# 04-Front_Panel_SFP_2.net
KiCad netlist of a schematic drawn in Altium Designer
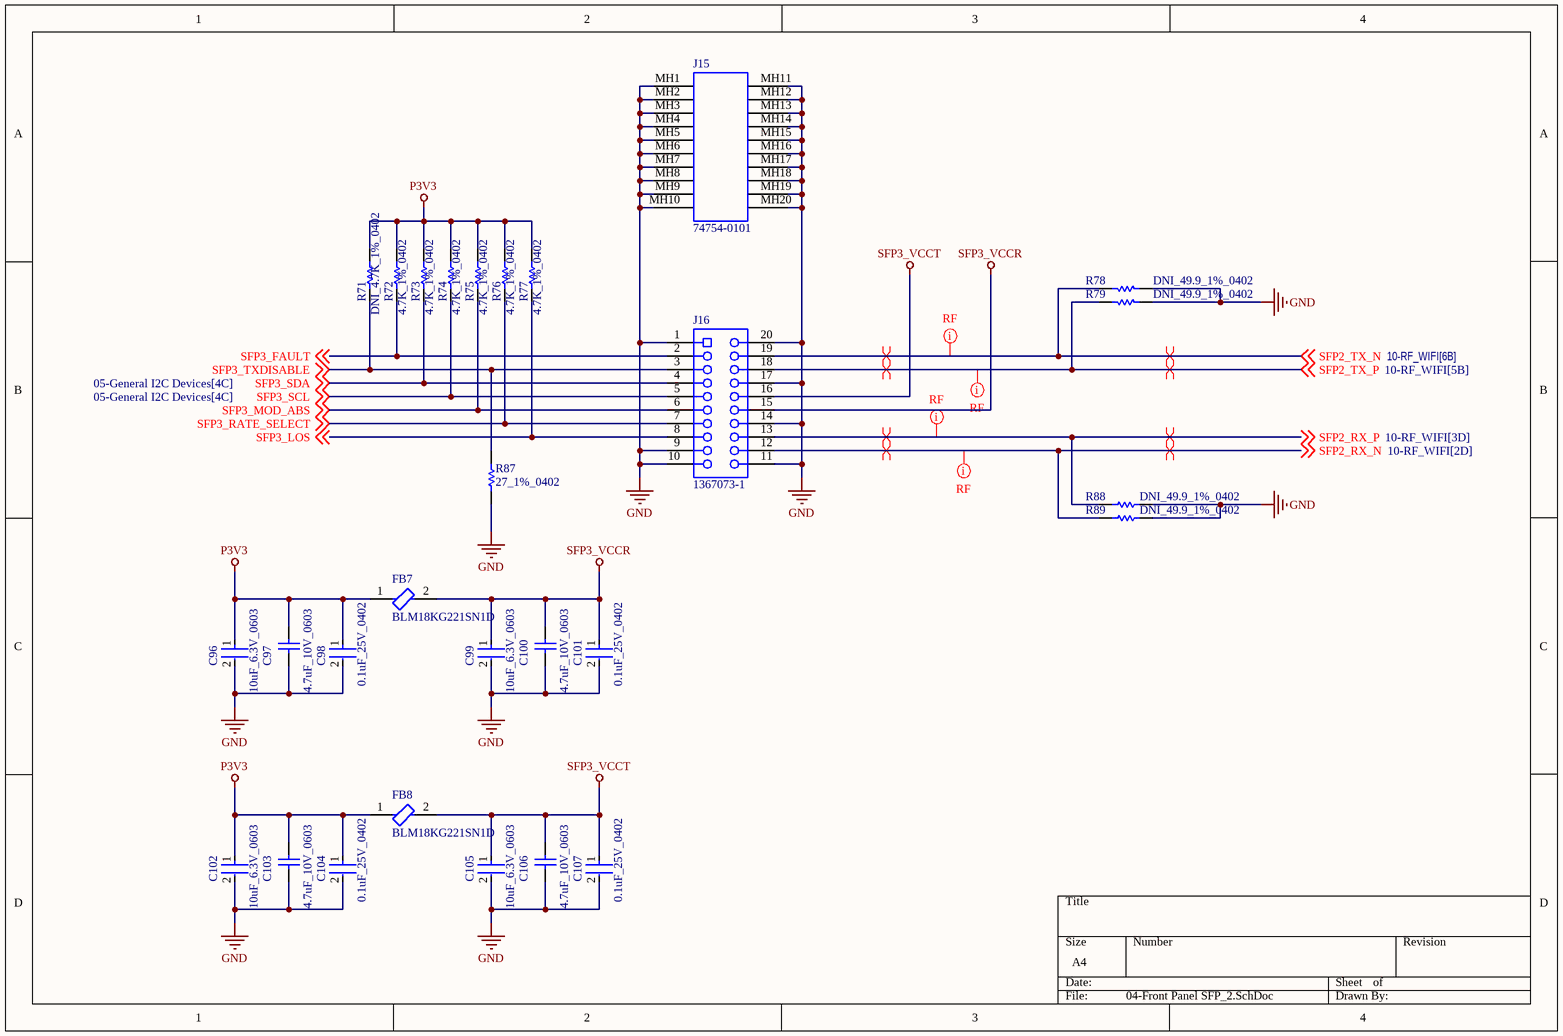
[diagram p0: 04-Front Panel SFP_2.SchDoc]

(export (version "E")
  (design (tool "Eeschema 10.0.6"))
  (components
    (comp (ref "C96")
      (value "10uF_6.3V_0603")
      (footprint "FP-C0603C106M9PACTU-MFG")
      (description "CAP CER 10UF 6.3V X5R 0603")
      (fields
        (field (name "MANUFACTURER PART NUMBER") "C0603C106M9PACTU")
        (field (name "MANUFACTURER") "Kemet")
      )
      (libsource (lib "Altium Content Vault") (part "b4654b650e69147ec39a6b967a45e02"))
    )
    (comp (ref "C97")
      (value "4.7uF_10V_0603")
      (footprint "CAPC1608X87X35NL15T15")
      (fields (field (name "PART NUMBER") "C0603C475K8PACTU") (field (name "MANUFACTURER") "Kemet"))
      (libsource (lib "Altium Content Vault") (part "CAP"))
    )
    (comp (ref "C98")
      (value "0.1uF_25V_0402")
      (footprint "FP-0402-L_1_0_1-W_0_5_0_1-IPC_C")
      (description "General Purpose Ceramic Capacitor, 0402, 100nF, 10%, X7R, 15%, 25V")
      (fields (field (name "VOLTAGE") "25V") (field (name "TOLERANCE") "10%"))
      (libsource (lib "Altium Content Vault") (part "b4654b650e69147ec39a6b967a45e02"))
    )
    (comp (ref "C99")
      (value "10uF_6.3V_0603")
      (footprint "FP-C0603C106M9PACTU-MFG")
      (description "CAP CER 10UF 6.3V X5R 0603")
      (fields
        (field (name "MANUFACTURER PART NUMBER") "C0603C106M9PACTU")
        (field (name "MANUFACTURER") "Kemet")
      )
      (libsource (lib "Altium Content Vault") (part "b4654b650e69147ec39a6b967a45e02"))
    )
    (comp (ref "C100")
      (value "4.7uF_10V_0603")
      (footprint "CAPC1608X87X35NL15T15")
      (fields (field (name "PART NUMBER") "C0603C475K8PACTU") (field (name "MANUFACTURER") "Kemet"))
      (libsource (lib "Altium Content Vault") (part "CAP"))
    )
    (comp (ref "C101")
      (value "0.1uF_25V_0402")
      (footprint "FP-0402-L_1_0_1-W_0_5_0_1-IPC_C")
      (description "General Purpose Ceramic Capacitor, 0402, 100nF, 10%, X7R, 15%, 25V")
      (fields (field (name "VOLTAGE") "25V") (field (name "TOLERANCE") "10%"))
      (libsource (lib "Altium Content Vault") (part "b4654b650e69147ec39a6b967a45e02"))
    )
    (comp (ref "C102")
      (value "10uF_6.3V_0603")
      (footprint "FP-C0603C106M9PACTU-MFG")
      (description "CAP CER 10UF 6.3V X5R 0603")
      (fields
        (field (name "MANUFACTURER PART NUMBER") "C0603C106M9PACTU")
        (field (name "MANUFACTURER") "Kemet")
      )
      (libsource (lib "Altium Content Vault") (part "b4654b650e69147ec39a6b967a45e02"))
    )
    (comp (ref "C103")
      (value "4.7uF_10V_0603")
      (footprint "CAPC1608X87X35NL15T15")
      (fields (field (name "PART NUMBER") "C0603C475K8PACTU") (field (name "MANUFACTURER") "Kemet"))
      (libsource (lib "Altium Content Vault") (part "CAP"))
    )
    (comp (ref "C104")
      (value "0.1uF_25V_0402")
      (footprint "FP-0402-L_1_0_1-W_0_5_0_1-IPC_C")
      (description "General Purpose Ceramic Capacitor, 0402, 100nF, 10%, X7R, 15%, 25V")
      (fields (field (name "VOLTAGE") "25V") (field (name "TOLERANCE") "10%"))
      (libsource (lib "Altium Content Vault") (part "b4654b650e69147ec39a6b967a45e02"))
    )
    (comp (ref "C105")
      (value "10uF_6.3V_0603")
      (footprint "FP-C0603C106M9PACTU-MFG")
      (description "CAP CER 10UF 6.3V X5R 0603")
      (fields
        (field (name "MANUFACTURER PART NUMBER") "C0603C106M9PACTU")
        (field (name "MANUFACTURER") "Kemet")
      )
      (libsource (lib "Altium Content Vault") (part "b4654b650e69147ec39a6b967a45e02"))
    )
    (comp (ref "C106")
      (value "4.7uF_10V_0603")
      (footprint "CAPC1608X87X35NL15T15")
      (fields (field (name "PART NUMBER") "C0603C475K8PACTU") (field (name "MANUFACTURER") "Kemet"))
      (libsource (lib "Altium Content Vault") (part "CAP"))
    )
    (comp (ref "C107")
      (value "0.1uF_25V_0402")
      (footprint "FP-0402-L_1_0_1-W_0_5_0_1-IPC_C")
      (description "General Purpose Ceramic Capacitor, 0402, 100nF, 10%, X7R, 15%, 25V")
      (fields (field (name "VOLTAGE") "25V") (field (name "TOLERANCE") "10%"))
      (libsource (lib "Altium Content Vault") (part "b4654b650e69147ec39a6b967a45e02"))
    )
    (comp (ref "FB7")
      (value "BLM18KG221SN1D")
      (footprint "FP-BLM18-0_15-t0_8-IPC_B")
      (description "Chip Ferrite Bead, 0603, 220Ω @ 100MHz, 0.05Ω, 25%, 2.2A")
      (fields (field (name "TOLERANCE") "25%"))
      (libsource (lib "Altium Content Vault") (part "5f30dd21d616792df468990f7003faa"))
    )
    (comp (ref "FB8")
      (value "BLM18KG221SN1D")
      (footprint "FP-BLM18-0_15-t0_8-IPC_B")
      (description "Chip Ferrite Bead, 0603, 220Ω @ 100MHz, 0.05Ω, 25%, 2.2A")
      (fields (field (name "TOLERANCE") "25%"))
      (libsource (lib "Altium Content Vault") (part "5f30dd21d616792df468990f7003faa"))
    )
    (comp (ref "J15")
      (value "74754-0101")
      (footprint "MOLX-74754-0101_V")
      (description "SFP+ Cage, Single Port, Height 10.85 mm, Tail Height 3.05 mm, -40 to 85 degC, RoHS, Tray")
      (libsource (lib "Altium Content Vault") (part "MOLX-74754-0101"))
    )
    (comp (ref "J16")
      (value "1367073-1")
      (footprint "TECO-1367073-1_V")
      (fields (field (name "MANUFACTURER") "TE Connectivity"))
      (libsource (lib "Altium Content Vault") (part "CN-2P-F-R20_B"))
    )
    (comp (ref "R71")
      (value "DNI_4.7K_1%_0402")
      (footprint "RESC1005X40X25NL10T10")
      (fields (field (name "MANUFACTURER") "Bourns") (field (name "PART NUMBER") "CR0402-FX-4701GLF"))
      (libsource (lib "Altium Content Vault") (part "RES"))
    )
    (comp (ref "R72")
      (value "4.7K_1%_0402")
      (footprint "RESC1005X40X25NL10T10")
      (fields (field (name "MANUFACTURER") "Bourns") (field (name "PART NUMBER") "CR0402-FX-4701GLF"))
      (libsource (lib "Altium Content Vault") (part "RES"))
    )
    (comp (ref "R73")
      (value "4.7K_1%_0402")
      (footprint "RESC1005X40X25NL10T10")
      (fields (field (name "MANUFACTURER") "Bourns") (field (name "PART NUMBER") "CR0402-FX-4701GLF"))
      (libsource (lib "Altium Content Vault") (part "RES"))
    )
    (comp (ref "R74")
      (value "4.7K_1%_0402")
      (footprint "RESC1005X40X25NL10T10")
      (fields (field (name "MANUFACTURER") "Bourns") (field (name "PART NUMBER") "CR0402-FX-4701GLF"))
      (libsource (lib "Altium Content Vault") (part "RES"))
    )
    (comp (ref "R75")
      (value "4.7K_1%_0402")
      (footprint "RESC1005X40X25NL10T10")
      (fields (field (name "MANUFACTURER") "Bourns") (field (name "PART NUMBER") "CR0402-FX-4701GLF"))
      (libsource (lib "Altium Content Vault") (part "RES"))
    )
    (comp (ref "R76")
      (value "4.7K_1%_0402")
      (footprint "RESC1005X40X25NL10T10")
      (fields (field (name "MANUFACTURER") "Bourns") (field (name "PART NUMBER") "CR0402-FX-4701GLF"))
      (libsource (lib "Altium Content Vault") (part "RES"))
    )
    (comp (ref "R77")
      (value "4.7K_1%_0402")
      (footprint "RESC1005X40X25NL10T10")
      (fields (field (name "MANUFACTURER") "Bourns") (field (name "PART NUMBER") "CR0402-FX-4701GLF"))
      (libsource (lib "Altium Content Vault") (part "RES"))
    )
    (comp (ref "R78")
      (value "DNI_49.9_1%_0402")
      (footprint "RESC1005X40X25NL10T10")
      (fields (field (name "PART NUMBER") "RK73H1ETTP49R9F") (field (name "MANUFACTURER") "KOA Speer"))
      (libsource (lib "Altium Content Vault") (part "RES"))
    )
    (comp (ref "R79")
      (value "DNI_49.9_1%_0402")
      (footprint "RESC1005X40X25NL10T10")
      (fields (field (name "PART NUMBER") "RK73H1ETTP49R9F") (field (name "MANUFACTURER") "KOA Speer"))
      (libsource (lib "Altium Content Vault") (part "RES"))
    )
    (comp (ref "R87")
      (value "27_1%_0402")
      (footprint "RESC1005X40X25NL05T05")
      (fields (field (name "PART NUMBER") "CRCW040227R0FKED") (field (name "MANUFACTURER") "Vishay Dale"))
      (libsource (lib "Altium Content Vault") (part "RES"))
    )
    (comp (ref "R88")
      (value "DNI_49.9_1%_0402")
      (footprint "RESC1005X40X25NL10T10")
      (fields (field (name "PART NUMBER") "RK73H1ETTP49R9F") (field (name "MANUFACTURER") "KOA Speer"))
      (libsource (lib "Altium Content Vault") (part "RES"))
    )
    (comp (ref "R89")
      (value "DNI_49.9_1%_0402")
      (footprint "RESC1005X40X25NL10T10")
      (fields (field (name "PART NUMBER") "RK73H1ETTP49R9F") (field (name "MANUFACTURER") "KOA Speer"))
      (libsource (lib "Altium Content Vault") (part "RES"))
    )
  )
  (nets
    (net (code "1") (name "GND") (class "Default")
      (node (ref "C100") (pin "1") (pinfunction "1_1") (pintype "passive"))
      (node (ref "C101") (pin "2") (pinfunction "2_2") (pintype "passive"))
      (node (ref "C102") (pin "2") (pinfunction "2_2") (pintype "passive"))
      (node (ref "C103") (pin "1") (pinfunction "1_1") (pintype "passive"))
      (node (ref "C104") (pin "2") (pinfunction "2_2") (pintype "passive"))
      (node (ref "C105") (pin "2") (pinfunction "2_2") (pintype "passive"))
      (node (ref "C106") (pin "1") (pinfunction "1_1") (pintype "passive"))
      (node (ref "C107") (pin "2") (pinfunction "2_2") (pintype "passive"))
      (node (ref "C96") (pin "2") (pinfunction "2_2") (pintype "passive"))
      (node (ref "C97") (pin "1") (pinfunction "1_1") (pintype "passive"))
      (node (ref "C98") (pin "2") (pinfunction "2_2") (pintype "passive"))
      (node (ref "C99") (pin "2") (pinfunction "2_2") (pintype "passive"))
      (node (ref "J15") (pin "MH1") (pinfunction "MH1_MH1") (pintype "passive"))
      (node (ref "J15") (pin "MH10") (pinfunction "MH10_MH10") (pintype "passive"))
      (node (ref "J15") (pin "MH11") (pinfunction "MH11_MH11") (pintype "passive"))
      (node (ref "J15") (pin "MH12") (pinfunction "MH12_MH12") (pintype "passive"))
      (node (ref "J15") (pin "MH13") (pinfunction "MH13_MH13") (pintype "passive"))
      (node (ref "J15") (pin "MH14") (pinfunction "MH14_MH14") (pintype "passive"))
      (node (ref "J15") (pin "MH15") (pinfunction "MH15_MH15") (pintype "passive"))
      (node (ref "J15") (pin "MH16") (pinfunction "MH16_MH16") (pintype "passive"))
      (node (ref "J15") (pin "MH17") (pinfunction "MH17_MH17") (pintype "passive"))
      (node (ref "J15") (pin "MH18") (pinfunction "MH18_MH18") (pintype "passive"))
      (node (ref "J15") (pin "MH19") (pinfunction "MH19_MH19") (pintype "passive"))
      (node (ref "J15") (pin "MH2") (pinfunction "MH2_MH2") (pintype "passive"))
      (node (ref "J15") (pin "MH20") (pinfunction "MH20_MH20") (pintype "passive"))
      (node (ref "J15") (pin "MH3") (pinfunction "MH3_MH3") (pintype "passive"))
      (node (ref "J15") (pin "MH4") (pinfunction "MH4_MH4") (pintype "passive"))
      (node (ref "J15") (pin "MH5") (pinfunction "MH5_MH5") (pintype "passive"))
      (node (ref "J15") (pin "MH6") (pinfunction "MH6_MH6") (pintype "passive"))
      (node (ref "J15") (pin "MH7") (pinfunction "MH7_MH7") (pintype "passive"))
      (node (ref "J15") (pin "MH8") (pinfunction "MH8_MH8") (pintype "passive"))
      (node (ref "J15") (pin "MH9") (pinfunction "MH9_MH9") (pintype "passive"))
      (node (ref "J16") (pin "1") (pinfunction "1_1") (pintype "passive"))
      (node (ref "J16") (pin "10") (pinfunction "10_10") (pintype "passive"))
      (node (ref "J16") (pin "11") (pinfunction "11_11") (pintype "passive"))
      (node (ref "J16") (pin "14") (pinfunction "14_14") (pintype "passive"))
      (node (ref "J16") (pin "17") (pinfunction "17_17") (pintype "passive"))
      (node (ref "J16") (pin "20") (pinfunction "20_20") (pintype "passive"))
      (node (ref "J16") (pin "9") (pinfunction "9_9") (pintype "passive"))
      (node (ref "R78") (pin "2") (pinfunction "2_2") (pintype "passive"))
      (node (ref "R79") (pin "2") (pinfunction "2_2") (pintype "passive"))
      (node (ref "R87") (pin "1") (pinfunction "1_1") (pintype "passive"))
      (node (ref "R88") (pin "2") (pinfunction "2_2") (pintype "passive"))
      (node (ref "R89") (pin "2") (pinfunction "2_2") (pintype "passive"))
    )
    (net (code "2") (name "P3V3") (class "Default")
      (node (ref "C102") (pin "1") (pinfunction "1_1") (pintype "passive"))
      (node (ref "C103") (pin "2") (pinfunction "2_2") (pintype "passive"))
      (node (ref "C104") (pin "1") (pinfunction "1_1") (pintype "passive"))
      (node (ref "C96") (pin "1") (pinfunction "1_1") (pintype "passive"))
      (node (ref "C97") (pin "2") (pinfunction "2_2") (pintype "passive"))
      (node (ref "C98") (pin "1") (pinfunction "1_1") (pintype "passive"))
      (node (ref "FB7") (pin "1") (pinfunction "1_1") (pintype "passive"))
      (node (ref "FB8") (pin "1") (pinfunction "1_1") (pintype "passive"))
      (node (ref "R71") (pin "1") (pinfunction "1_1") (pintype "passive"))
      (node (ref "R72") (pin "1") (pinfunction "1_1") (pintype "passive"))
      (node (ref "R73") (pin "1") (pinfunction "1_1") (pintype "passive"))
      (node (ref "R74") (pin "1") (pinfunction "1_1") (pintype "passive"))
      (node (ref "R75") (pin "1") (pinfunction "1_1") (pintype "passive"))
      (node (ref "R76") (pin "1") (pinfunction "1_1") (pintype "passive"))
      (node (ref "R77") (pin "1") (pinfunction "1_1") (pintype "passive"))
    )
    (net (code "3") (name "SFP2_RX_N") (class "Default")
      (node (ref "J16") (pin "12") (pinfunction "12_12") (pintype "passive"))
      (node (ref "R89") (pin "1") (pinfunction "1_1") (pintype "passive"))
    )
    (net (code "4") (name "SFP2_RX_P") (class "Default")
      (node (ref "J16") (pin "13") (pinfunction "13_13") (pintype "passive"))
      (node (ref "R88") (pin "1") (pinfunction "1_1") (pintype "passive"))
    )
    (net (code "5") (name "SFP2_TX_N") (class "Default")
      (node (ref "J16") (pin "19") (pinfunction "19_19") (pintype "passive"))
      (node (ref "R78") (pin "1") (pinfunction "1_1") (pintype "passive"))
    )
    (net (code "6") (name "SFP2_TX_P") (class "Default")
      (node (ref "J16") (pin "18") (pinfunction "18_18") (pintype "passive"))
      (node (ref "R79") (pin "1") (pinfunction "1_1") (pintype "passive"))
    )
    (net (code "7") (name "SFP3_FAULT") (class "Default")
      (node (ref "J16") (pin "2") (pinfunction "2_2") (pintype "passive"))
      (node (ref "R72") (pin "2") (pinfunction "2_2") (pintype "passive"))
    )
    (net (code "8") (name "SFP3_LOS") (class "Default")
      (node (ref "J16") (pin "8") (pinfunction "8_8") (pintype "passive"))
      (node (ref "R77") (pin "2") (pinfunction "2_2") (pintype "passive"))
    )
    (net (code "9") (name "SFP3_MOD_ABS") (class "Default")
      (node (ref "J16") (pin "6") (pinfunction "6_6") (pintype "passive"))
      (node (ref "R75") (pin "2") (pinfunction "2_2") (pintype "passive"))
    )
    (net (code "10") (name "SFP3_RATE_SELECT") (class "Default")
      (node (ref "J16") (pin "7") (pinfunction "7_7") (pintype "passive"))
      (node (ref "R76") (pin "2") (pinfunction "2_2") (pintype "passive"))
    )
    (net (code "11") (name "SFP3_SCL") (class "Default")
      (node (ref "J16") (pin "5") (pinfunction "5_5") (pintype "passive"))
      (node (ref "R74") (pin "2") (pinfunction "2_2") (pintype "passive"))
    )
    (net (code "12") (name "SFP3_SDA") (class "Default")
      (node (ref "J16") (pin "4") (pinfunction "4_4") (pintype "passive"))
      (node (ref "R73") (pin "2") (pinfunction "2_2") (pintype "passive"))
    )
    (net (code "13") (name "SFP3_TXDISABLE") (class "Default")
      (node (ref "J16") (pin "3") (pinfunction "3_3") (pintype "passive"))
      (node (ref "R71") (pin "2") (pinfunction "2_2") (pintype "passive"))
      (node (ref "R87") (pin "2") (pinfunction "2_2") (pintype "passive"))
    )
    (net (code "14") (name "SFP3_VCCR") (class "Default")
      (node (ref "C100") (pin "2") (pinfunction "2_2") (pintype "passive"))
      (node (ref "C101") (pin "1") (pinfunction "1_1") (pintype "passive"))
      (node (ref "C99") (pin "1") (pinfunction "1_1") (pintype "passive"))
      (node (ref "FB7") (pin "2") (pinfunction "2_2") (pintype "passive"))
      (node (ref "J16") (pin "15") (pinfunction "15_15") (pintype "passive"))
    )
    (net (code "15") (name "SFP3_VCCT") (class "Default")
      (node (ref "C105") (pin "1") (pinfunction "1_1") (pintype "passive"))
      (node (ref "C106") (pin "2") (pinfunction "2_2") (pintype "passive"))
      (node (ref "C107") (pin "1") (pinfunction "1_1") (pintype "passive"))
      (node (ref "FB8") (pin "2") (pinfunction "2_2") (pintype "passive"))
      (node (ref "J16") (pin "16") (pinfunction "16_16") (pintype "passive"))
    )
  )
)
